# Ethernet.net
KiCad netlist of a schematic drawn in Altium Designer
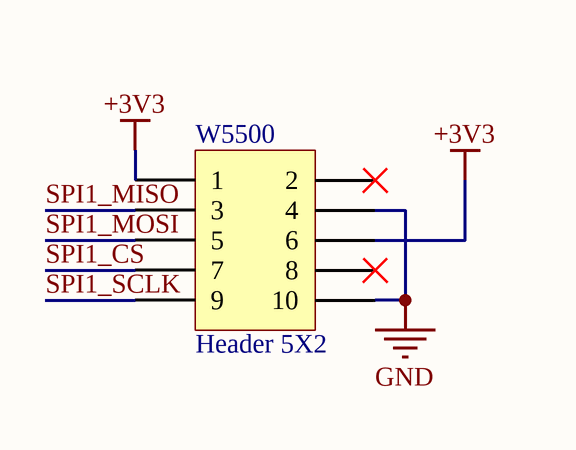
[diagram p0: Ethernet.SchDoc]

(export (version "E")
  (design (tool "Eeschema 10.0.6"))
  (components
    (comp (ref "W5500")
      (value "Header 5X2")
      (footprint "HDR2X5")
      (description "Header, 5-Pin, Dual row")
      (fields (field (name "PUBLISHER") "Altium Limited"))
      (libsource (lib "My Library") (part "Header 5X2"))
    )
  )
  (nets
    (net (code "1") (name "+3V3") (class "Default")
      (node (ref "W5500") (pin "1") (pinfunction "1_1") (pintype "passive"))
      (node (ref "W5500") (pin "6") (pinfunction "6_6") (pintype "passive"))
    )
    (net (code "2") (name "/SPI1_CS") (class "Default")
      (node (ref "W5500") (pin "7") (pinfunction "7_7") (pintype "passive"))
    )
    (net (code "3") (name "/SPI1_MISO") (class "Default")
      (node (ref "W5500") (pin "3") (pinfunction "3_3") (pintype "passive"))
    )
    (net (code "4") (name "/SPI1_MOSI") (class "Default")
      (node (ref "W5500") (pin "5") (pinfunction "5_5") (pintype "passive"))
    )
    (net (code "5") (name "/SPI1_SCLK") (class "Default")
      (node (ref "W5500") (pin "9") (pinfunction "9_9") (pintype "passive"))
    )
    (net (code "6") (name "GND") (class "Default")
      (node (ref "W5500") (pin "10") (pinfunction "10_10") (pintype "passive"))
      (node (ref "W5500") (pin "4") (pinfunction "4_4") (pintype "passive"))
    )
    (net (code "7") (name "unconnected-(W5500-Pad2)") (class "Default")
      (node (ref "W5500") (pin "2") (pinfunction "2_2") (pintype "passive+no_connect"))
    )
    (net (code "8") (name "unconnected-(W5500-Pad8)") (class "Default")
      (node (ref "W5500") (pin "8") (pinfunction "8_8") (pintype "passive+no_connect"))
    )
  )
)
